# Connectors.net
KiCad netlist of a schematic drawn in Altium Designer
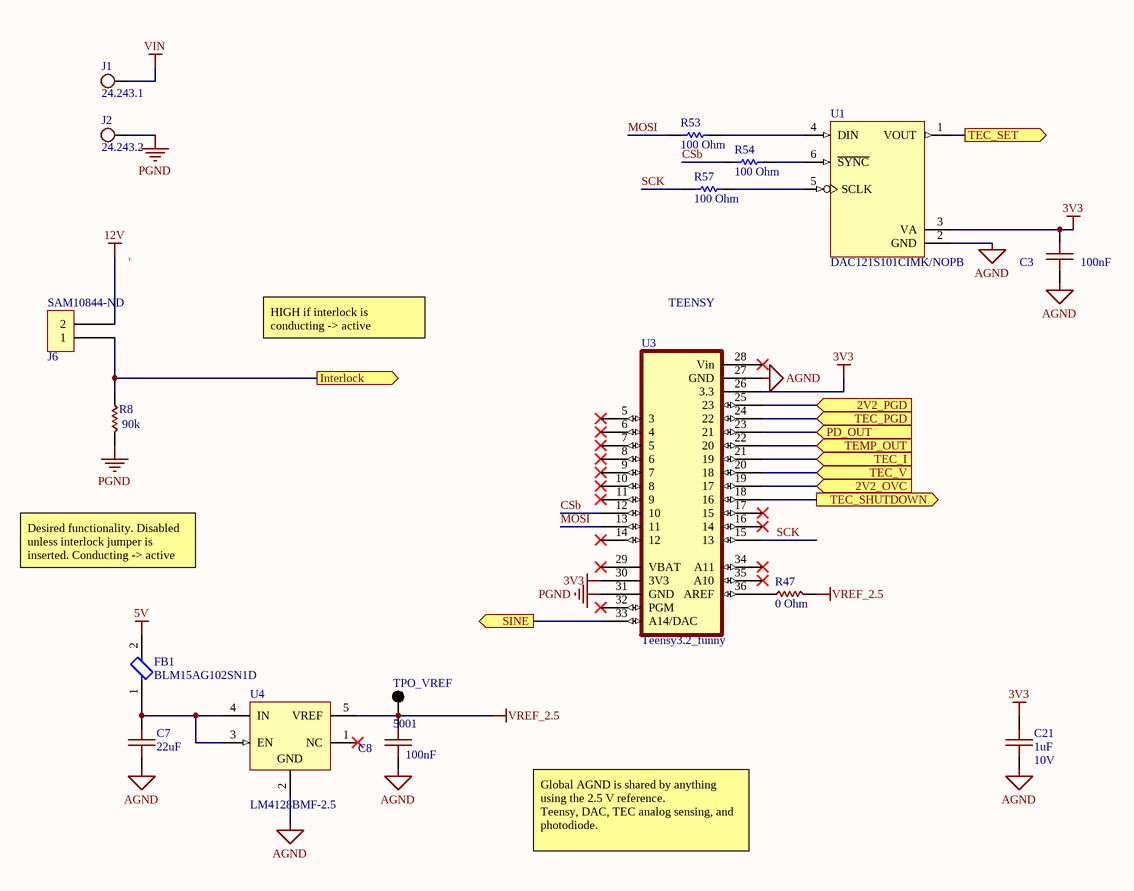
[diagram p0: Connectors.SchDoc]

(export (version "E")
  (design (tool "Eeschema 10.0.6"))
  (components
    (comp (ref "C3")
      (value "100nF")
      (footprint "0603 B")
      (description "603 Capacitor")
      (libsource (lib "PSSL3") (part "CAP 0603"))
    )
    (comp (ref "C7")
      (value "22uF")
      (footprint "1210")
      (description "1210 Capacitor")
      (libsource (lib "PSSL3") (part "CAP 1210"))
    )
    (comp (ref "C8")
      (value "100nF")
      (footprint "0603 B")
      (description "603 Capacitor")
      (libsource (lib "PSSL3") (part "CAP 0603"))
    )
    (comp (ref "C21")
      (value "1uF")
      (footprint "0603 B")
      (description "603 Capacitor")
      (fields (field (name "VOLTAGE") "10V"))
      (libsource (lib "PSSL3") (part "CAP 0603"))
    )
    (comp (ref "FB1")
      (value "BLM15AG102SN1D")
      (footprint "FP-BLM15-MFG")
      (description "FERRITE BEAD 1 KOHM 0402 1LN")
      (fields
        (field (name "OCTOPART") "https://octopart.com/blm15ag102sn1d-murata-368316")
        (field (name "TOLERANCE") "25%")
      )
      (libsource (lib "Altium Content Vault") (part "5f30dd21d616792df468990f7003faa"))
    )
    (comp (ref "J1")
      (value "24.243.1")
      (footprint "BANANA RD")
      (description "Banana jack, PCB mount right angle")
      (libsource (lib "PSSL3") (part "BANANA RED"))
    )
    (comp (ref "J2")
      (value "24.243.2")
      (footprint "BANANA BK")
      (description "Banana jack, PCB mount right angle")
      (libsource (lib "PSSL3") (part "BANANA BLACK"))
    )
    (comp (ref "J6")
      (value "SIL02")
      (footprint "SIL02")
      (description "Conn Unshrouded Header HDR 2 POS 2.54mm Solder ST Top Entry Thru-Hole Bag")
      (fields
        (field (name "SUPPLIER PART NUMBER 1") "SAM10844-ND")
        (field (name "MANUFACTURER") "Samtec")
        (field (name "MANUFACTURER PART NUMBER") "TSW-102-07-F-S")
      )
      (libsource (lib "PSSL3") (part "SIL02"))
    )
    (comp (ref "R8")
      (value "90k")
      (footprint "0603")
      (description "603 Resistor")
      (libsource (lib "PSSL3") (part "RES 0603"))
    )
    (comp (ref "R47")
      (value "0 Ohm")
      (footprint "0603")
      (description "603 Resistor")
      (libsource (lib "PSSL3") (part "RES 0603"))
    )
    (comp (ref "R53")
      (value "100 Ohm")
      (footprint "RESC1608X55X30LL15T15")
      (fields (field (name "MANUFACTURER") "Panasonic") (field (name "PART NUMBER") "ERJ-3EKF1000V"))
      (libsource (lib "Altium Content Vault") (part "RES"))
    )
    (comp (ref "R54")
      (value "100 Ohm")
      (footprint "RESC1608X55X30LL15T15")
      (fields (field (name "MANUFACTURER") "Panasonic") (field (name "PART NUMBER") "ERJ-3EKF1000V"))
      (libsource (lib "Altium Content Vault") (part "RES"))
    )
    (comp (ref "R57")
      (value "100 Ohm")
      (footprint "RESC1608X55X30LL15T15")
      (fields (field (name "MANUFACTURER") "Panasonic") (field (name "PART NUMBER") "ERJ-3EKF1000V"))
      (libsource (lib "Altium Content Vault") (part "RES"))
    )
    (comp (ref "TPO_VREF")
      (value "5001")
      (footprint "KSTN-5001")
      (description "Test Point, Black, 1-Pin THD, RoHS, Bulk")
      (fields (field (name "MANUFACTURER") "Keystone"))
      (libsource (lib "Altium Content Vault") (part "KSTN-TP-5001"))
    )
    (comp (ref "U1")
      (value "DAC121S101CIMK/NOPB")
      (footprint "MK06A_N")
      (description "12-Bit Micro Power, RRO Digital-to-Analog Converter, 6-pin Tiny SOT23, Pb-Free")
      (fields (field (name "MANUFACTURER") "National Semiconductor"))
      (libsource (lib "Altium Content Vault") (part "CON-DAC-DAC121S101-6"))
    )
    (comp (ref "U3")
      (value "Teensy3.2_funny")
      (footprint "Teensy32_funny")
      (libsource (lib "BeaconBoard") (part "Teensy3.2_funny"))
    )
    (comp (ref "U4")
      (value "LM4128BMF-2.5")
      (footprint "DBV0005A_N")
      (description "Precision Micropower Series Voltage Reference, 5-pin SOT-23")
      (fields (field (name "MANUFACTURER") "Texas Instruments"))
      (libsource (lib "Altium Content Vault") (part "PM-REF-LM4128-SOT5"))
    )
  )
  (nets
    (net (code "1") (name "/2V2_OVC") (class "Default")
      (node (ref "U3") (pin "19") (pinfunction "17_19") (pintype "bidirectional"))
    )
    (net (code "2") (name "/2V2_PGD") (class "Default")
      (node (ref "U3") (pin "25") (pinfunction "23_25") (pintype "bidirectional"))
    )
    (net (code "3") (name "/CSb") (class "Default")
      (node (ref "R54") (pin "1") (pinfunction "1_1") (pintype "passive"))
      (node (ref "U3") (pin "12") (pinfunction "10_12") (pintype "bidirectional"))
    )
    (net (code "4") (name "/Interlock") (class "Default")
      (node (ref "J6") (pin "1") (pinfunction "1_1") (pintype "passive"))
      (node (ref "R8") (pin "2") (pintype "passive"))
    )
    (net (code "5") (name "/MOSI") (class "Default")
      (node (ref "R53") (pin "1") (pinfunction "1_1") (pintype "passive"))
      (node (ref "U3") (pin "13") (pinfunction "11_13") (pintype "bidirectional"))
    )
    (net (code "6") (name "/PD_OUT") (class "Default")
      (node (ref "U3") (pin "23") (pinfunction "21_23") (pintype "bidirectional"))
    )
    (net (code "7") (name "/SCK") (class "Default")
      (node (ref "R57") (pin "1") (pinfunction "1_1") (pintype "passive"))
      (node (ref "U3") (pin "15") (pinfunction "13_15") (pintype "bidirectional"))
    )
    (net (code "8") (name "/SINE") (class "Default")
      (node (ref "U3") (pin "33") (pinfunction "A14/DAC_33") (pintype "bidirectional"))
    )
    (net (code "9") (name "/TEC_I") (class "Default")
      (node (ref "U3") (pin "21") (pinfunction "19_21") (pintype "bidirectional"))
    )
    (net (code "10") (name "/TEC_PGD") (class "Default")
      (node (ref "U3") (pin "24") (pinfunction "22_24") (pintype "bidirectional"))
    )
    (net (code "11") (name "/TEC_SET") (class "Default")
      (node (ref "U1") (pin "1") (pinfunction "VOUT_1") (pintype "output"))
    )
    (net (code "12") (name "/TEC_SHUTDOWN") (class "Default")
      (node (ref "U3") (pin "18") (pinfunction "16_18") (pintype "bidirectional"))
    )
    (net (code "13") (name "/TEC_V") (class "Default")
      (node (ref "U3") (pin "20") (pinfunction "18_20") (pintype "bidirectional"))
    )
    (net (code "14") (name "/TEMP_OUT") (class "Default")
      (node (ref "U3") (pin "22") (pinfunction "20_22") (pintype "bidirectional"))
    )
    (net (code "15") (name "3V3") (class "Default")
      (node (ref "C21") (pin "2") (pintype "passive"))
      (node (ref "C3") (pin "1") (pintype "passive"))
      (node (ref "U1") (pin "3") (pinfunction "VA_3") (pintype "power_in"))
      (node (ref "U3") (pin "26") (pinfunction "3.3_26") (pintype "power_in"))
      (node (ref "U3") (pin "30") (pinfunction "3V3_30") (pintype "power_in"))
    )
    (net (code "16") (name "5V") (class "Default")
      (node (ref "FB1") (pin "2") (pinfunction "2_2") (pintype "passive"))
    )
    (net (code "17") (name "12V") (class "Default")
      (node (ref "J6") (pin "2") (pinfunction "2_2") (pintype "passive"))
    )
    (net (code "18") (name "AGND") (class "Default")
      (node (ref "C21") (pin "1") (pintype "passive"))
      (node (ref "C3") (pin "2") (pintype "passive"))
      (node (ref "C7") (pin "2") (pintype "passive"))
      (node (ref "C8") (pin "2") (pintype "passive"))
      (node (ref "U1") (pin "2") (pinfunction "GND_2") (pintype "power_in"))
      (node (ref "U3") (pin "27") (pinfunction "GND_27") (pintype "power_in"))
      (node (ref "U4") (pin "2") (pinfunction "GND_2") (pintype "power_in"))
    )
    (net (code "19") (name "Net-(U1-DIN)") (class "Default")
      (node (ref "R53") (pin "2") (pinfunction "2_2") (pintype "passive"))
      (node (ref "U1") (pin "4") (pinfunction "DIN_4") (pintype "input"))
    )
    (net (code "20") (name "Net-(U1-SCLK)") (class "Default")
      (node (ref "R57") (pin "2") (pinfunction "2_2") (pintype "passive"))
      (node (ref "U1") (pin "5") (pinfunction "SCLK_5") (pintype "input"))
    )
    (net (code "21") (name "Net-(U1-~{SYNC})") (class "Default")
      (node (ref "R54") (pin "2") (pinfunction "2_2") (pintype "passive"))
      (node (ref "U1") (pin "6") (pinfunction "~{SYNC}_6") (pintype "input"))
    )
    (net (code "22") (name "Net-(U3-AREF)") (class "Default")
      (node (ref "R47") (pin "2") (pintype "passive"))
      (node (ref "U3") (pin "36") (pinfunction "AREF_36") (pintype "bidirectional"))
    )
    (net (code "23") (name "Net-(U4-EN)") (class "Default")
      (node (ref "C7") (pin "1") (pintype "passive"))
      (node (ref "FB1") (pin "1") (pinfunction "1_1") (pintype "passive"))
      (node (ref "U4") (pin "3") (pinfunction "EN_3") (pintype "input"))
      (node (ref "U4") (pin "4") (pinfunction "IN_4") (pintype "power_in"))
    )
    (net (code "24") (name "PGND") (class "Default")
      (node (ref "J2") (pin "1") (pinfunction "TP_1") (pintype "passive"))
      (node (ref "R8") (pin "1") (pintype "passive"))
      (node (ref "U3") (pin "31") (pinfunction "GND_31") (pintype "power_in"))
    )
    (net (code "25") (name "VIN") (class "Default")
      (node (ref "J1") (pin "1") (pinfunction "TP_1") (pintype "passive"))
    )
    (net (code "26") (name "VREF_2.5") (class "Default")
      (node (ref "C8") (pin "1") (pintype "passive"))
      (node (ref "R47") (pin "1") (pintype "passive"))
      (node (ref "TPO_VREF") (pin "1") (pintype "passive"))
      (node (ref "U4") (pin "5") (pinfunction "VREF_5") (pintype "power_in"))
    )
    (net (code "27") (name "unconnected-(U3-3-Pad5)") (class "Default")
      (node (ref "U3") (pin "5") (pinfunction "3_5") (pintype "bidirectional+no_connect"))
    )
    (net (code "28") (name "unconnected-(U3-4-Pad6)") (class "Default")
      (node (ref "U3") (pin "6") (pinfunction "4_6") (pintype "bidirectional+no_connect"))
    )
    (net (code "29") (name "unconnected-(U3-5-Pad7)") (class "Default")
      (node (ref "U3") (pin "7") (pinfunction "5_7") (pintype "bidirectional+no_connect"))
    )
    (net (code "30") (name "unconnected-(U3-6-Pad8)") (class "Default")
      (node (ref "U3") (pin "8") (pinfunction "6_8") (pintype "bidirectional+no_connect"))
    )
    (net (code "31") (name "unconnected-(U3-7-Pad9)") (class "Default")
      (node (ref "U3") (pin "9") (pinfunction "7_9") (pintype "bidirectional+no_connect"))
    )
    (net (code "32") (name "unconnected-(U3-8-Pad10)") (class "Default")
      (node (ref "U3") (pin "10") (pinfunction "8_10") (pintype "bidirectional+no_connect"))
    )
    (net (code "33") (name "unconnected-(U3-9-Pad11)") (class "Default")
      (node (ref "U3") (pin "11") (pinfunction "9_11") (pintype "bidirectional+no_connect"))
    )
    (net (code "34") (name "unconnected-(U3-12-Pad14)") (class "Default")
      (node (ref "U3") (pin "14") (pinfunction "12_14") (pintype "bidirectional+no_connect"))
    )
    (net (code "35") (name "unconnected-(U3-14-Pad16)") (class "Default")
      (node (ref "U3") (pin "16") (pinfunction "14_16") (pintype "bidirectional+no_connect"))
    )
    (net (code "36") (name "unconnected-(U3-15-Pad17)") (class "Default")
      (node (ref "U3") (pin "17") (pinfunction "15_17") (pintype "bidirectional+no_connect"))
    )
    (net (code "37") (name "unconnected-(U3-A10-Pad35)") (class "Default")
      (node (ref "U3") (pin "35") (pinfunction "A10_35") (pintype "bidirectional+no_connect"))
    )
    (net (code "38") (name "unconnected-(U3-A11-Pad34)") (class "Default")
      (node (ref "U3") (pin "34") (pinfunction "A11_34") (pintype "bidirectional+no_connect"))
    )
    (net (code "39") (name "unconnected-(U3-PGM-Pad32)") (class "Default")
      (node (ref "U3") (pin "32") (pinfunction "PGM_32") (pintype "bidirectional+no_connect"))
    )
    (net (code "40") (name "unconnected-(U3-VBAT-Pad29)") (class "Default")
      (node (ref "U3") (pin "29") (pinfunction "VBAT_29") (pintype "power_in+no_connect"))
    )
    (net (code "41") (name "unconnected-(U3-Vin-Pad28)") (class "Default")
      (node (ref "U3") (pin "28") (pinfunction "Vin_28") (pintype "power_in+no_connect"))
    )
    (net (code "42") (name "unconnected-(U4-NC-Pad1)") (class "Default")
      (node (ref "U4") (pin "1") (pinfunction "NC_1") (pintype "passive+no_connect"))
    )
  )
)
